# investigator_control_board.net
KiCad netlist of a schematic drawn in Altium Designer
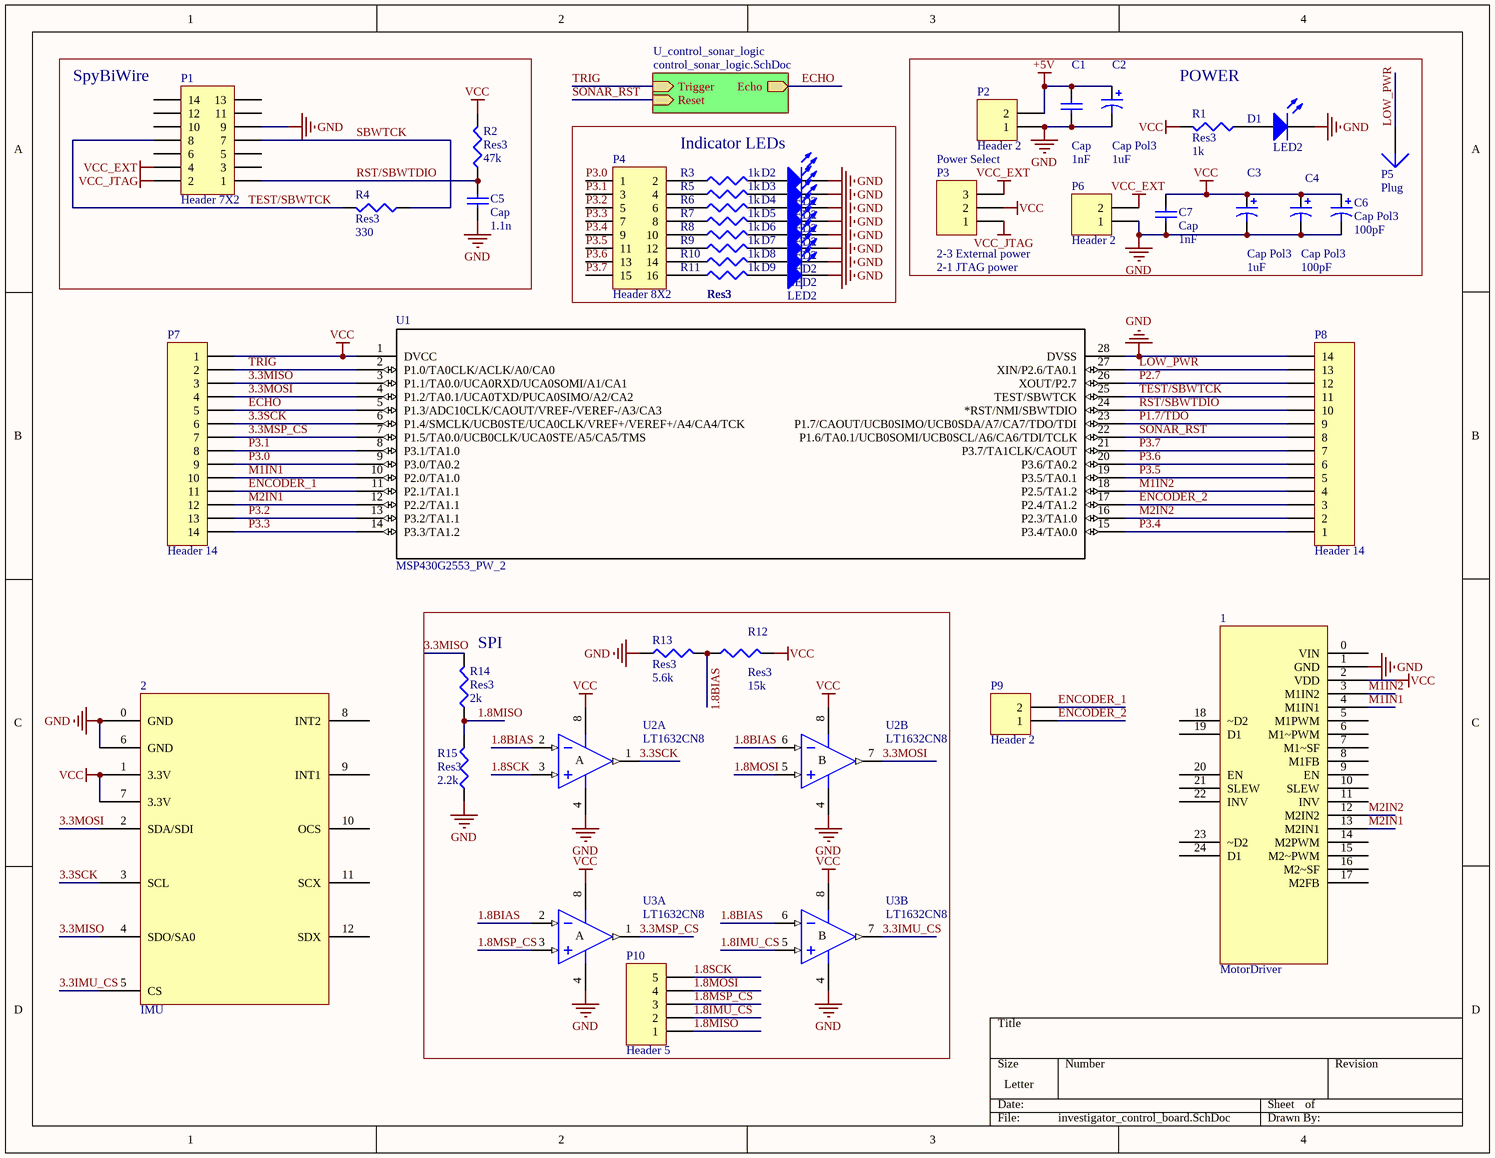
[diagram p0: investigator_control_board.SchDoc]

(export (version "E")
  (design (tool "Eeschema 10.0.6"))
  (components
    (comp (ref "1")
      (value "MotorDriver")
      (footprint "MotorControlHeader")
      (libsource (lib "control_board") (part "MotorDriver"))
    )
    (comp (ref "2") (value "IMU") (footprint "IMU") (libsource (lib "control_board") (part "IMU")))
    (comp (ref "C1")
      (value "Cap")
      (footprint "C0805")
      (description "Capacitor")
      (fields (field (name "ALTIUM_VALUE") "1nF") (field (name "PUBLISHER") "Altium Limited"))
      (libsource (lib "Miscellaneous Devices") (part "Cap"))
    )
    (comp (ref "C2")
      (value "Cap Pol3")
      (footprint "AXIAL-0.3")
      (description "Polarized Capacitor (Surface Mount)")
      (fields (field (name "ALTIUM_VALUE") "1uF") (field (name "PUBLISHER") "Altium Limited"))
      (libsource (lib "Miscellaneous Devices") (part "Cap Pol3"))
    )
    (comp (ref "C3")
      (value "Cap Pol3")
      (footprint "AXIAL-0.3")
      (description "Polarized Capacitor (Surface Mount)")
      (fields (field (name "ALTIUM_VALUE") "1uF") (field (name "PUBLISHER") "Altium Limited"))
      (libsource (lib "Miscellaneous Devices") (part "Cap Pol3"))
    )
    (comp (ref "C4")
      (value "Cap Pol3")
      (footprint "AXIAL-0.3")
      (description "Polarized Capacitor (Surface Mount)")
      (fields (field (name "ALTIUM_VALUE") "100pF") (field (name "PUBLISHER") "Altium Limited"))
      (libsource (lib "Miscellaneous Devices") (part "Cap Pol3"))
    )
    (comp (ref "C5")
      (value "Cap")
      (footprint "C0805")
      (description "Capacitor")
      (fields (field (name "ALTIUM_VALUE") "1.1n") (field (name "PUBLISHER") "Altium Limited"))
      (libsource (lib "Miscellaneous Devices") (part "Cap"))
    )
    (comp (ref "C6")
      (value "Cap Pol3")
      (footprint "AXIAL-0.3")
      (description "Polarized Capacitor (Surface Mount)")
      (fields (field (name "ALTIUM_VALUE") "100pF") (field (name "PUBLISHER") "Altium Limited"))
      (libsource (lib "Miscellaneous Devices") (part "Cap Pol3"))
    )
    (comp (ref "C7")
      (value "Cap")
      (footprint "C0805")
      (description "Capacitor")
      (fields (field (name "ALTIUM_VALUE") "1nF") (field (name "PUBLISHER") "Altium Limited"))
      (libsource (lib "Miscellaneous Devices") (part "Cap"))
    )
    (comp (ref "D1")
      (value "LED2")
      (footprint "3.2X1.6X1.1")
      (description "Typical RED, GREEN, YELLOW, AMBER GaAs LED")
      (fields (field (name "PUBLISHER") "Altium Limited"))
      (libsource (lib "Miscellaneous Devices") (part "LED2"))
    )
    (comp (ref "D2")
      (value "LED2")
      (footprint "3.2X1.6X1.1")
      (description "Typical RED, GREEN, YELLOW, AMBER GaAs LED")
      (fields (field (name "PUBLISHER") "Altium Limited"))
      (libsource (lib "Miscellaneous Devices") (part "LED2"))
    )
    (comp (ref "D3")
      (value "LED2")
      (footprint "3.2X1.6X1.1")
      (description "Typical RED, GREEN, YELLOW, AMBER GaAs LED")
      (fields (field (name "PUBLISHER") "Altium Limited"))
      (libsource (lib "Miscellaneous Devices") (part "LED2"))
    )
    (comp (ref "D4")
      (value "LED2")
      (footprint "3.2X1.6X1.1")
      (description "Typical RED, GREEN, YELLOW, AMBER GaAs LED")
      (fields (field (name "PUBLISHER") "Altium Limited"))
      (libsource (lib "Miscellaneous Devices") (part "LED2"))
    )
    (comp (ref "D5")
      (value "LED2")
      (footprint "3.2X1.6X1.1")
      (description "Typical RED, GREEN, YELLOW, AMBER GaAs LED")
      (fields (field (name "PUBLISHER") "Altium Limited"))
      (libsource (lib "Miscellaneous Devices") (part "LED2"))
    )
    (comp (ref "D6")
      (value "LED2")
      (footprint "3.2X1.6X1.1")
      (description "Typical RED, GREEN, YELLOW, AMBER GaAs LED")
      (fields (field (name "PUBLISHER") "Altium Limited"))
      (libsource (lib "Miscellaneous Devices") (part "LED2"))
    )
    (comp (ref "D7")
      (value "LED2")
      (footprint "3.2X1.6X1.1")
      (description "Typical RED, GREEN, YELLOW, AMBER GaAs LED")
      (fields (field (name "PUBLISHER") "Altium Limited"))
      (libsource (lib "Miscellaneous Devices") (part "LED2"))
    )
    (comp (ref "D8")
      (value "LED2")
      (footprint "3.2X1.6X1.1")
      (description "Typical RED, GREEN, YELLOW, AMBER GaAs LED")
      (fields (field (name "PUBLISHER") "Altium Limited"))
      (libsource (lib "Miscellaneous Devices") (part "LED2"))
    )
    (comp (ref "D9")
      (value "LED2")
      (footprint "3.2X1.6X1.1")
      (description "Typical RED, GREEN, YELLOW, AMBER GaAs LED")
      (fields (field (name "PUBLISHER") "Altium Limited"))
      (libsource (lib "Miscellaneous Devices") (part "LED2"))
    )
    (comp (ref "P1")
      (value "Header 7X2")
      (footprint "HDR2X7")
      (description "Header, 7-Pin, Dual row")
      (fields (field (name "PUBLISHER") "Altium Limited"))
      (libsource (lib "Miscellaneous Connectors") (part "Header 7X2"))
    )
    (comp (ref "P2")
      (value "Header 2")
      (footprint "HDR1X2")
      (description "Header, 2-Pin")
      (fields (field (name "PUBLISHER") "Altium Limited"))
      (libsource (lib "Miscellaneous Connectors") (part "Header 2"))
    )
    (comp (ref "P3")
      (value "Power Select")
      (footprint "HDR1X3")
      (description "Header, 3-Pin")
      (fields (field (name "PUBLISHER") "Altium Limited"))
      (libsource (lib "Miscellaneous Connectors") (part "Header 3"))
    )
    (comp (ref "P4")
      (value "Header 8X2")
      (footprint "HDR2X8")
      (description "Header, 8-Pin, Dual row")
      (fields (field (name "PUBLISHER") "Altium Limited"))
      (libsource (lib "Miscellaneous Connectors") (part "Header 8X2"))
    )
    (comp (ref "P5")
      (value "Plug")
      (footprint "PIN1")
      (fields (field (name "PUBLISHER") "Altium Limited"))
      (libsource (lib "Miscellaneous Connectors") (part "Plug"))
    )
    (comp (ref "P6")
      (value "Header 2")
      (footprint "HDR1X2")
      (description "Header, 2-Pin")
      (fields (field (name "PUBLISHER") "Altium Limited"))
      (libsource (lib "Miscellaneous Connectors") (part "Header 2"))
    )
    (comp (ref "P7")
      (value "Header 14")
      (footprint "HDR1X14")
      (description "Header, 14-Pin")
      (fields (field (name "PUBLISHER") "Altium Limited"))
      (libsource (lib "") (part "Header 14_1"))
    )
    (comp (ref "P8")
      (value "Header 14")
      (footprint "HDR1X14")
      (description "Header, 14-Pin")
      (fields (field (name "PUBLISHER") "Altium Limited"))
      (libsource (lib "Miscellaneous Connectors") (part "Header 14"))
    )
    (comp (ref "P9")
      (value "Header 2")
      (footprint "HDR1X2")
      (description "Header, 2-Pin")
      (fields (field (name "PUBLISHER") "Altium Limited"))
      (libsource (lib "Miscellaneous Connectors") (part "Header 2"))
    )
    (comp (ref "P10")
      (value "Header 5")
      (footprint "HDR1X5")
      (description "Header, 5-Pin")
      (fields (field (name "PUBLISHER") "Altium Limited"))
      (libsource (lib "Miscellaneous Connectors") (part "Header 5"))
    )
    (comp (ref "R1")
      (value "Res3")
      (footprint "6-0805_M")
      (description "Resistor")
      (fields (field (name "ALTIUM_VALUE") "1k") (field (name "PUBLISHER") "Altium Limited"))
      (libsource (lib "Miscellaneous Devices") (part "Res3"))
    )
    (comp (ref "R2")
      (value "Res3")
      (footprint "6-0805_M")
      (description "Resistor")
      (fields (field (name "ALTIUM_VALUE") "47k") (field (name "PUBLISHER") "Altium Limited"))
      (libsource (lib "Miscellaneous Devices") (part "Res3"))
    )
    (comp (ref "R3")
      (value "Res3")
      (footprint "6-0805_N")
      (description "Resistor")
      (fields (field (name "ALTIUM_VALUE") "1k") (field (name "PUBLISHER") "Altium Limited"))
      (libsource (lib "Miscellaneous Devices") (part "Res3"))
    )
    (comp (ref "R4")
      (value "Res3")
      (footprint "6-0805_M")
      (description "Resistor")
      (fields (field (name "ALTIUM_VALUE") "330") (field (name "PUBLISHER") "Altium Limited"))
      (libsource (lib "Miscellaneous Devices") (part "Res3"))
    )
    (comp (ref "R5")
      (value "Res3")
      (footprint "6-0805_N")
      (description "Resistor")
      (fields (field (name "ALTIUM_VALUE") "1k") (field (name "PUBLISHER") "Altium Limited"))
      (libsource (lib "Miscellaneous Devices") (part "Res3"))
    )
    (comp (ref "R6")
      (value "Res3")
      (footprint "6-0805_N")
      (description "Resistor")
      (fields (field (name "ALTIUM_VALUE") "1k") (field (name "PUBLISHER") "Altium Limited"))
      (libsource (lib "Miscellaneous Devices") (part "Res3"))
    )
    (comp (ref "R7")
      (value "Res3")
      (footprint "6-0805_N")
      (description "Resistor")
      (fields (field (name "ALTIUM_VALUE") "1k") (field (name "PUBLISHER") "Altium Limited"))
      (libsource (lib "Miscellaneous Devices") (part "Res3"))
    )
    (comp (ref "R8")
      (value "Res3")
      (footprint "6-0805_N")
      (description "Resistor")
      (fields (field (name "ALTIUM_VALUE") "1k") (field (name "PUBLISHER") "Altium Limited"))
      (libsource (lib "Miscellaneous Devices") (part "Res3"))
    )
    (comp (ref "R9")
      (value "Res3")
      (footprint "6-0805_N")
      (description "Resistor")
      (fields (field (name "ALTIUM_VALUE") "1k") (field (name "PUBLISHER") "Altium Limited"))
      (libsource (lib "Miscellaneous Devices") (part "Res3"))
    )
    (comp (ref "R10")
      (value "Res3")
      (footprint "6-0805_N")
      (description "Resistor")
      (fields (field (name "ALTIUM_VALUE") "1k") (field (name "PUBLISHER") "Altium Limited"))
      (libsource (lib "Miscellaneous Devices") (part "Res3"))
    )
    (comp (ref "R11")
      (value "Res3")
      (footprint "6-0805_N")
      (description "Resistor")
      (fields (field (name "ALTIUM_VALUE") "1k") (field (name "PUBLISHER") "Altium Limited"))
      (libsource (lib "Miscellaneous Devices") (part "Res3"))
    )
    (comp (ref "R12")
      (value "Res3")
      (footprint "6-0805_N")
      (description "Resistor")
      (fields (field (name "ALTIUM_VALUE") "15k") (field (name "PUBLISHER") "Altium Limited"))
      (libsource (lib "Miscellaneous Devices") (part "Res3"))
    )
    (comp (ref "R13")
      (value "Res3")
      (footprint "6-0805_N")
      (description "Resistor")
      (fields (field (name "ALTIUM_VALUE") "5.6k") (field (name "PUBLISHER") "Altium Limited"))
      (libsource (lib "Miscellaneous Devices") (part "Res3"))
    )
    (comp (ref "R14")
      (value "Res3")
      (footprint "6-0805_N")
      (description "Resistor")
      (fields (field (name "ALTIUM_VALUE") "2k") (field (name "PUBLISHER") "Altium Limited"))
      (libsource (lib "Miscellaneous Devices") (part "Res3"))
    )
    (comp (ref "R15")
      (value "Res3")
      (footprint "6-0805_N")
      (description "Resistor")
      (fields (field (name "ALTIUM_VALUE") "2.2k") (field (name "PUBLISHER") "Altium Limited"))
      (libsource (lib "Miscellaneous Devices") (part "Res3"))
    )
    (comp (ref "U1")
      (value "MSP430G2553_PW_2")
      (footprint "PW28")
      (description "Imported")
      (fields
        (field (name "MANUFACTURER_PART_NUMBER") "msp430g2553_pw_28")
        (field (name "GENERIC_PART_NUMBER") "MSP430G2553")
      )
      (libsource (lib "MSP430G2253") (part "MSP430G2553_PW_2"))
    )
    (comp (ref "U2")
      (value "LT1632CN8")
      (footprint "DIP-8")
      (description "45MHz, 45V/µs, Dual Rail-to-Rail Input and Output Precision Operational Amplifier")
      (fields (field (name "PUBLISHER") "Altium Limited"))
      (libsource (lib "ECE Lib (1)") (part "LT1632CN8"))
    )
    (comp (ref "U3")
      (value "LT1632CN8")
      (footprint "DIP-8")
      (description "45MHz, 45V/µs, Dual Rail-to-Rail Input and Output Precision Operational Amplifier")
      (fields (field (name "PUBLISHER") "Altium Limited"))
      (libsource (lib "ECE Lib (1)") (part "LT1632CN8"))
    )
  )
  (nets
    (net (code "1") (name "+5V") (class "Default")
      (node (ref "C1") (pin "2") (pinfunction "2_2") (pintype "passive"))
      (node (ref "C2") (pin "1") (pinfunction "1_1") (pintype "passive"))
      (node (ref "P2") (pin "2") (pinfunction "2_2") (pintype "passive"))
    )
    (net (code "2") (name "/1.8BIAS") (class "Default")
      (node (ref "R12") (pin "1") (pinfunction "1_1") (pintype "passive"))
      (node (ref "R13") (pin "2") (pinfunction "2_2") (pintype "passive"))
      (node (ref "U2") (pin "2") (pinfunction "IN-_2") (pintype "input"))
      (node (ref "U2") (pin "6") (pinfunction "IN-_6") (pintype "input"))
      (node (ref "U3") (pin "2") (pinfunction "IN-_2") (pintype "input"))
      (node (ref "U3") (pin "6") (pinfunction "IN-_6") (pintype "input"))
    )
    (net (code "3") (name "/1.8IMU_CS") (class "Default")
      (node (ref "P10") (pin "2") (pinfunction "2_2") (pintype "passive"))
      (node (ref "U3") (pin "5") (pinfunction "IN+_5") (pintype "input"))
    )
    (net (code "4") (name "/1.8MISO") (class "Default")
      (node (ref "P10") (pin "1") (pinfunction "1_1") (pintype "passive"))
      (node (ref "R14") (pin "1") (pinfunction "1_1") (pintype "passive"))
      (node (ref "R15") (pin "2") (pinfunction "2_2") (pintype "passive"))
    )
    (net (code "5") (name "/1.8MOSI") (class "Default")
      (node (ref "P10") (pin "4") (pinfunction "4_4") (pintype "passive"))
      (node (ref "U2") (pin "5") (pinfunction "IN+_5") (pintype "input"))
    )
    (net (code "6") (name "/1.8MSP_CS") (class "Default")
      (node (ref "P10") (pin "3") (pinfunction "3_3") (pintype "passive"))
      (node (ref "U3") (pin "3") (pinfunction "IN+_3") (pintype "input"))
    )
    (net (code "7") (name "/1.8SCK") (class "Default")
      (node (ref "P10") (pin "5") (pinfunction "5_5") (pintype "passive"))
      (node (ref "U2") (pin "3") (pinfunction "IN+_3") (pintype "input"))
    )
    (net (code "8") (name "/3.3IMU_CS") (class "Default")
      (node (ref "2") (pin "5") (pinfunction "CS_5") (pintype "passive"))
      (node (ref "U3") (pin "7") (pinfunction "OUT_7") (pintype "output"))
    )
    (net (code "9") (name "/3.3MISO") (class "Default")
      (node (ref "2") (pin "4") (pinfunction "SDO/SA0_4") (pintype "passive"))
      (node (ref "P7") (pin "3") (pinfunction "3_3") (pintype "passive"))
      (node (ref "R14") (pin "2") (pinfunction "2_2") (pintype "passive"))
      (node (ref "U1") (pin "3") (pinfunction "P1.1/TA0.0/UCA0RXD/UCA0SOMI/A1/CA1_3") (pintype "bidirectional"))
    )
    (net (code "10") (name "/3.3MOSI") (class "Default")
      (node (ref "2") (pin "2") (pinfunction "SDA/SDI_2") (pintype "passive"))
      (node (ref "P7") (pin "4") (pinfunction "4_4") (pintype "passive"))
      (node (ref "U1") (pin "4") (pinfunction "P1.2/TA0.1/UCA0TXD/PUCA0SIMO/A2/CA2_4") (pintype "bidirectional"))
      (node (ref "U2") (pin "7") (pinfunction "OUT_7") (pintype "output"))
    )
    (net (code "11") (name "/3.3MSP_CS") (class "Default")
      (node (ref "P7") (pin "7") (pinfunction "7_7") (pintype "passive"))
      (node (ref "U1") (pin "7") (pinfunction "P1.5/TA0.0/UCB0CLK/UCA0STE/A5/CA5/TMS_7") (pintype "bidirectional"))
      (node (ref "U3") (pin "1") (pinfunction "OUT_1") (pintype "output"))
    )
    (net (code "12") (name "/3.3SCK") (class "Default")
      (node (ref "2") (pin "3") (pinfunction "SCL_3") (pintype "passive"))
      (node (ref "P7") (pin "6") (pinfunction "6_6") (pintype "passive"))
      (node (ref "U1") (pin "6") (pinfunction "P1.4/SMCLK/UCB0STE/UCA0CLK/VREF+/VEREF+/A4/CA4/TCK_6") (pintype "bidirectional"))
      (node (ref "U2") (pin "1") (pinfunction "OUT_1") (pintype "output"))
    )
    (net (code "13") (name "/ECHO") (class "Default")
      (node (ref "P7") (pin "5") (pinfunction "5_5") (pintype "passive"))
      (node (ref "U1") (pin "5") (pinfunction "P1.3/ADC10CLK/CAOUT/VREF-/VEREF-/A3/CA3_5") (pintype "bidirectional"))
    )
    (net (code "14") (name "/ENCODER_1") (class "Default")
      (node (ref "P7") (pin "11") (pinfunction "11_11") (pintype "passive"))
      (node (ref "P9") (pin "2") (pinfunction "2_2") (pintype "passive"))
      (node (ref "U1") (pin "11") (pinfunction "P2.1/TA1.1_11") (pintype "bidirectional"))
    )
    (net (code "15") (name "/ENCODER_2") (class "Default")
      (node (ref "P8") (pin "3") (pinfunction "3_3") (pintype "passive"))
      (node (ref "P9") (pin "1") (pinfunction "1_1") (pintype "passive"))
      (node (ref "U1") (pin "17") (pinfunction "P2.4/TA1.2_17") (pintype "bidirectional"))
    )
    (net (code "16") (name "/LOW_PWR") (class "Default")
      (node (ref "P5") (pin "1") (pinfunction "1_1") (pintype "passive"))
      (node (ref "P8") (pin "13") (pinfunction "13_13") (pintype "passive"))
      (node (ref "U1") (pin "27") (pinfunction "XIN/P2.6/TA0.1_27") (pintype "bidirectional"))
    )
    (net (code "17") (name "/M1IN1") (class "Default")
      (node (ref "1") (pin "4") (pinfunction "M1IN1_4") (pintype "passive"))
      (node (ref "P7") (pin "10") (pinfunction "10_10") (pintype "passive"))
      (node (ref "U1") (pin "10") (pinfunction "P2.0/TA1.0_10") (pintype "bidirectional"))
    )
    (net (code "18") (name "/M1IN2") (class "Default")
      (node (ref "1") (pin "3") (pinfunction "M1IN2_3") (pintype "passive"))
      (node (ref "P8") (pin "4") (pinfunction "4_4") (pintype "passive"))
      (node (ref "U1") (pin "18") (pinfunction "P2.5/TA1.2_18") (pintype "bidirectional"))
    )
    (net (code "19") (name "/M2IN1") (class "Default")
      (node (ref "1") (pin "13") (pinfunction "M2IN1_13") (pintype "passive"))
      (node (ref "P7") (pin "12") (pinfunction "12_12") (pintype "passive"))
      (node (ref "U1") (pin "12") (pinfunction "P2.2/TA1.1_12") (pintype "bidirectional"))
    )
    (net (code "20") (name "/M2IN2") (class "Default")
      (node (ref "1") (pin "12") (pinfunction "M2IN2_12") (pintype "passive"))
      (node (ref "P8") (pin "2") (pinfunction "2_2") (pintype "passive"))
      (node (ref "U1") (pin "16") (pinfunction "P2.3/TA1.0_16") (pintype "bidirectional"))
    )
    (net (code "21") (name "/P1.7{slash}TDO") (class "Default")
      (node (ref "P8") (pin "9") (pinfunction "9_9") (pintype "passive"))
      (node (ref "U1") (pin "23") (pinfunction "P1.7/CAOUT/UCB0SIMO/UCB0SDA/A7/CA7/TDO/TDI_23") (pintype "bidirectional"))
    )
    (net (code "22") (name "/P2.7") (class "Default")
      (node (ref "P8") (pin "12") (pinfunction "12_12") (pintype "passive"))
      (node (ref "U1") (pin "26") (pinfunction "XOUT/P2.7_26") (pintype "bidirectional"))
    )
    (net (code "23") (name "/P3.0") (class "Default")
      (node (ref "P4") (pin "1") (pinfunction "1_1") (pintype "passive"))
      (node (ref "P7") (pin "9") (pinfunction "9_9") (pintype "passive"))
      (node (ref "U1") (pin "9") (pinfunction "P3.0/TA0.2_9") (pintype "bidirectional"))
    )
    (net (code "24") (name "/P3.1") (class "Default")
      (node (ref "P4") (pin "3") (pinfunction "3_3") (pintype "passive"))
      (node (ref "P7") (pin "8") (pinfunction "8_8") (pintype "passive"))
      (node (ref "U1") (pin "8") (pinfunction "P3.1/TA1.0_8") (pintype "bidirectional"))
    )
    (net (code "25") (name "/P3.2") (class "Default")
      (node (ref "P4") (pin "5") (pinfunction "5_5") (pintype "passive"))
      (node (ref "P7") (pin "13") (pinfunction "13_13") (pintype "passive"))
      (node (ref "U1") (pin "13") (pinfunction "P3.2/TA1.1_13") (pintype "bidirectional"))
    )
    (net (code "26") (name "/P3.3") (class "Default")
      (node (ref "P4") (pin "7") (pinfunction "7_7") (pintype "passive"))
      (node (ref "P7") (pin "14") (pinfunction "14_14") (pintype "passive"))
      (node (ref "U1") (pin "14") (pinfunction "P3.3/TA1.2_14") (pintype "bidirectional"))
    )
    (net (code "27") (name "/P3.4") (class "Default")
      (node (ref "P4") (pin "9") (pinfunction "9_9") (pintype "passive"))
      (node (ref "P8") (pin "1") (pinfunction "1_1") (pintype "passive"))
      (node (ref "U1") (pin "15") (pinfunction "P3.4/TA0.0_15") (pintype "bidirectional"))
    )
    (net (code "28") (name "/P3.5") (class "Default")
      (node (ref "P4") (pin "11") (pinfunction "11_11") (pintype "passive"))
      (node (ref "P8") (pin "5") (pinfunction "5_5") (pintype "passive"))
      (node (ref "U1") (pin "19") (pinfunction "P3.5/TA0.1_19") (pintype "bidirectional"))
    )
    (net (code "29") (name "/P3.6") (class "Default")
      (node (ref "P4") (pin "13") (pinfunction "13_13") (pintype "passive"))
      (node (ref "P8") (pin "6") (pinfunction "6_6") (pintype "passive"))
      (node (ref "U1") (pin "20") (pinfunction "P3.6/TA0.2_20") (pintype "bidirectional"))
    )
    (net (code "30") (name "/P3.7") (class "Default")
      (node (ref "P4") (pin "15") (pinfunction "15_15") (pintype "passive"))
      (node (ref "P8") (pin "7") (pinfunction "7_7") (pintype "passive"))
      (node (ref "U1") (pin "21") (pinfunction "P3.7/TA1CLK/CAOUT_21") (pintype "bidirectional"))
    )
    (net (code "31") (name "/RST{slash}SBWTDIO") (class "Default")
      (node (ref "C5") (pin "2") (pinfunction "2_2") (pintype "passive"))
      (node (ref "P1") (pin "1") (pinfunction "1_1") (pintype "passive"))
      (node (ref "P8") (pin "10") (pinfunction "10_10") (pintype "passive"))
      (node (ref "R2") (pin "1") (pinfunction "1_1") (pintype "passive"))
      (node (ref "U1") (pin "24") (pinfunction "*RST/NMI/SBWTDIO_24") (pintype "bidirectional"))
    )
    (net (code "32") (name "/SBWTCK") (class "Default")
      (node (ref "P1") (pin "7") (pinfunction "7_7") (pintype "passive"))
      (node (ref "R4") (pin "1") (pinfunction "1_1") (pintype "passive"))
    )
    (net (code "33") (name "/SONAR_RST") (class "Default")
      (node (ref "P8") (pin "8") (pinfunction "8_8") (pintype "passive"))
      (node (ref "U1") (pin "22") (pinfunction "P1.6/TA0.1/UCB0SOMI/UCB0SCL/A6/CA6/TDI/TCLK_22") (pintype "bidirectional"))
    )
    (net (code "34") (name "/TEST{slash}SBWTCK") (class "Default")
      (node (ref "P1") (pin "8") (pinfunction "8_8") (pintype "passive"))
      (node (ref "P8") (pin "11") (pinfunction "11_11") (pintype "passive"))
      (node (ref "R4") (pin "2") (pinfunction "2_2") (pintype "passive"))
      (node (ref "U1") (pin "25") (pinfunction "TEST/SBWTCK_25") (pintype "bidirectional"))
    )
    (net (code "35") (name "/TRIG") (class "Default")
      (node (ref "P7") (pin "2") (pinfunction "2_2") (pintype "passive"))
      (node (ref "U1") (pin "2") (pinfunction "P1.0/TA0CLK/ACLK/A0/CA0_2") (pintype "bidirectional"))
    )
    (net (code "36") (name "GND") (class "Default")
      (node (ref "1") (pin "1") (pinfunction "GND_1") (pintype "passive"))
      (node (ref "2") (pin "0") (pinfunction "GND_0") (pintype "passive"))
      (node (ref "2") (pin "6") (pinfunction "GND_6") (pintype "passive"))
      (node (ref "C1") (pin "1") (pinfunction "1_1") (pintype "passive"))
      (node (ref "C2") (pin "2") (pinfunction "2_2") (pintype "passive"))
      (node (ref "C3") (pin "2") (pinfunction "2_2") (pintype "passive"))
      (node (ref "C4") (pin "2") (pinfunction "2_2") (pintype "passive"))
      (node (ref "C5") (pin "1") (pinfunction "1_1") (pintype "passive"))
      (node (ref "C6") (pin "2") (pinfunction "2_2") (pintype "passive"))
      (node (ref "C7") (pin "1") (pinfunction "1_1") (pintype "passive"))
      (node (ref "D1") (pin "2") (pinfunction "K_2") (pintype "passive"))
      (node (ref "D2") (pin "2") (pinfunction "K_2") (pintype "passive"))
      (node (ref "D3") (pin "2") (pinfunction "K_2") (pintype "passive"))
      (node (ref "D4") (pin "2") (pinfunction "K_2") (pintype "passive"))
      (node (ref "D5") (pin "2") (pinfunction "K_2") (pintype "passive"))
      (node (ref "D6") (pin "2") (pinfunction "K_2") (pintype "passive"))
      (node (ref "D7") (pin "2") (pinfunction "K_2") (pintype "passive"))
      (node (ref "D8") (pin "2") (pinfunction "K_2") (pintype "passive"))
      (node (ref "D9") (pin "2") (pinfunction "K_2") (pintype "passive"))
      (node (ref "P1") (pin "9") (pinfunction "9_9") (pintype "passive"))
      (node (ref "P2") (pin "1") (pinfunction "1_1") (pintype "passive"))
      (node (ref "P6") (pin "1") (pinfunction "1_1") (pintype "passive"))
      (node (ref "P8") (pin "14") (pinfunction "14_14") (pintype "passive"))
      (node (ref "R13") (pin "1") (pinfunction "1_1") (pintype "passive"))
      (node (ref "R15") (pin "1") (pinfunction "1_1") (pintype "passive"))
      (node (ref "U1") (pin "28") (pinfunction "DVSS_28") (pintype "power_in"))
      (node (ref "U2") (pin "4") (pinfunction "V-_4") (pintype "power_in"))
      (node (ref "U3") (pin "4") (pinfunction "V-_4") (pintype "power_in"))
    )
    (net (code "37") (name "Net-(D1-A)") (class "Default")
      (node (ref "D1") (pin "1") (pinfunction "A_1") (pintype "passive"))
      (node (ref "R1") (pin "1") (pinfunction "1_1") (pintype "passive"))
    )
    (net (code "38") (name "Net-(D2-A)") (class "Default")
      (node (ref "D2") (pin "1") (pinfunction "A_1") (pintype "passive"))
      (node (ref "R3") (pin "2") (pinfunction "2_2") (pintype "passive"))
    )
    (net (code "39") (name "Net-(D3-A)") (class "Default")
      (node (ref "D3") (pin "1") (pinfunction "A_1") (pintype "passive"))
      (node (ref "R5") (pin "2") (pinfunction "2_2") (pintype "passive"))
    )
    (net (code "40") (name "Net-(D4-A)") (class "Default")
      (node (ref "D4") (pin "1") (pinfunction "A_1") (pintype "passive"))
      (node (ref "R6") (pin "2") (pinfunction "2_2") (pintype "passive"))
    )
    (net (code "41") (name "Net-(D5-A)") (class "Default")
      (node (ref "D5") (pin "1") (pinfunction "A_1") (pintype "passive"))
      (node (ref "R7") (pin "2") (pinfunction "2_2") (pintype "passive"))
    )
    (net (code "42") (name "Net-(D6-A)") (class "Default")
      (node (ref "D6") (pin "1") (pinfunction "A_1") (pintype "passive"))
      (node (ref "R8") (pin "2") (pinfunction "2_2") (pintype "passive"))
    )
    (net (code "43") (name "Net-(D7-A)") (class "Default")
      (node (ref "D7") (pin "1") (pinfunction "A_1") (pintype "passive"))
      (node (ref "R9") (pin "2") (pinfunction "2_2") (pintype "passive"))
    )
    (net (code "44") (name "Net-(D8-A)") (class "Default")
      (node (ref "D8") (pin "1") (pinfunction "A_1") (pintype "passive"))
      (node (ref "R10") (pin "2") (pinfunction "2_2") (pintype "passive"))
    )
    (net (code "45") (name "Net-(D9-A)") (class "Default")
      (node (ref "D9") (pin "1") (pinfunction "A_1") (pintype "passive"))
      (node (ref "R11") (pin "2") (pinfunction "2_2") (pintype "passive"))
    )
    (net (code "46") (name "Net-(P4-Pad2)") (class "Default")
      (node (ref "P4") (pin "2") (pinfunction "2_2") (pintype "passive"))
      (node (ref "R3") (pin "1") (pinfunction "1_1") (pintype "passive"))
    )
    (net (code "47") (name "Net-(P4-Pad4)") (class "Default")
      (node (ref "P4") (pin "4") (pinfunction "4_4") (pintype "passive"))
      (node (ref "R5") (pin "1") (pinfunction "1_1") (pintype "passive"))
    )
    (net (code "48") (name "Net-(P4-Pad6)") (class "Default")
      (node (ref "P4") (pin "6") (pinfunction "6_6") (pintype "passive"))
      (node (ref "R6") (pin "1") (pinfunction "1_1") (pintype "passive"))
    )
    (net (code "49") (name "Net-(P4-Pad8)") (class "Default")
      (node (ref "P4") (pin "8") (pinfunction "8_8") (pintype "passive"))
      (node (ref "R7") (pin "1") (pinfunction "1_1") (pintype "passive"))
    )
    (net (code "50") (name "Net-(P4-Pad10)") (class "Default")
      (node (ref "P4") (pin "10") (pinfunction "10_10") (pintype "passive"))
      (node (ref "R8") (pin "1") (pinfunction "1_1") (pintype "passive"))
    )
    (net (code "51") (name "Net-(P4-Pad12)") (class "Default")
      (node (ref "P4") (pin "12") (pinfunction "12_12") (pintype "passive"))
      (node (ref "R9") (pin "1") (pinfunction "1_1") (pintype "passive"))
    )
    (net (code "52") (name "Net-(P4-Pad14)") (class "Default")
      (node (ref "P4") (pin "14") (pinfunction "14_14") (pintype "passive"))
      (node (ref "R10") (pin "1") (pinfunction "1_1") (pintype "passive"))
    )
    (net (code "53") (name "Net-(P4-Pad16)") (class "Default")
      (node (ref "P4") (pin "16") (pinfunction "16_16") (pintype "passive"))
      (node (ref "R11") (pin "1") (pinfunction "1_1") (pintype "passive"))
    )
    (net (code "54") (name "VCC") (class "Default")
      (node (ref "1") (pin "2") (pinfunction "VDD_2") (pintype "passive"))
      (node (ref "2") (pin "1") (pinfunction "3.3V_1") (pintype "passive"))
      (node (ref "2") (pin "7") (pinfunction "3.3V_7") (pintype "passive"))
      (node (ref "C3") (pin "1") (pinfunction "1_1") (pintype "passive"))
      (node (ref "C4") (pin "1") (pinfunction "1_1") (pintype "passive"))
      (node (ref "C6") (pin "1") (pinfunction "1_1") (pintype "passive"))
      (node (ref "C7") (pin "2") (pinfunction "2_2") (pintype "passive"))
      (node (ref "P3") (pin "2") (pinfunction "2_2") (pintype "passive"))
      (node (ref "P7") (pin "1") (pinfunction "1_1") (pintype "passive"))
      (node (ref "R1") (pin "2") (pinfunction "2_2") (pintype "passive"))
      (node (ref "R12") (pin "2") (pinfunction "2_2") (pintype "passive"))
      (node (ref "R2") (pin "2") (pinfunction "2_2") (pintype "passive"))
      (node (ref "U1") (pin "1") (pinfunction "DVCC_1") (pintype "power_in"))
      (node (ref "U2") (pin "8") (pinfunction "V+_8") (pintype "power_in"))
      (node (ref "U3") (pin "8") (pinfunction "V+_8") (pintype "power_in"))
    )
    (net (code "55") (name "VCC_EXT") (class "Default")
      (node (ref "P1") (pin "4") (pinfunction "4_4") (pintype "passive"))
      (node (ref "P3") (pin "3") (pinfunction "3_3") (pintype "passive"))
      (node (ref "P6") (pin "2") (pinfunction "2_2") (pintype "passive"))
    )
    (net (code "56") (name "VCC_JTAG") (class "Default")
      (node (ref "P1") (pin "2") (pinfunction "2_2") (pintype "passive"))
      (node (ref "P3") (pin "1") (pinfunction "1_1") (pintype "passive"))
    )
    (net (code "57") (name "unconnected-(1-D1-Pad19)") (class "Default")
      (node (ref "1") (pin "19") (pinfunction "D1_19") (pintype "passive"))
    )
    (net (code "58") (name "unconnected-(1-D1-Pad24)") (class "Default")
      (node (ref "1") (pin "24") (pinfunction "D1_24") (pintype "passive"))
    )
    (net (code "59") (name "unconnected-(1-EN-Pad9)") (class "Default")
      (node (ref "1") (pin "9") (pinfunction "EN_9") (pintype "passive"))
    )
    (net (code "60") (name "unconnected-(1-EN-Pad20)") (class "Default")
      (node (ref "1") (pin "20") (pinfunction "EN_20") (pintype "passive"))
    )
    (net (code "61") (name "unconnected-(1-INV-Pad11)") (class "Default")
      (node (ref "1") (pin "11") (pinfunction "INV_11") (pintype "passive"))
    )
    (net (code "62") (name "unconnected-(1-INV-Pad22)") (class "Default")
      (node (ref "1") (pin "22") (pinfunction "INV_22") (pintype "passive"))
    )
    (net (code "63") (name "unconnected-(1-M1FB-Pad8)") (class "Default")
      (node (ref "1") (pin "8") (pinfunction "M1FB_8") (pintype "passive"))
    )
    (net (code "64") (name "unconnected-(1-M1PWM-Pad5)") (class "Default")
      (node (ref "1") (pin "5") (pinfunction "M1PWM_5") (pintype "passive"))
    )
    (net (code "65") (name "unconnected-(1-M1~PWM-Pad6)") (class "Default")
      (node (ref "1") (pin "6") (pinfunction "M1~PWM_6") (pintype "passive"))
    )
    (net (code "66") (name "unconnected-(1-M1~SF-Pad7)") (class "Default")
      (node (ref "1") (pin "7") (pinfunction "M1~SF_7") (pintype "passive"))
    )
    (net (code "67") (name "unconnected-(1-M2FB-Pad17)") (class "Default")
      (node (ref "1") (pin "17") (pinfunction "M2FB_17") (pintype "passive"))
    )
    (net (code "68") (name "unconnected-(1-M2PWM-Pad14)") (class "Default")
      (node (ref "1") (pin "14") (pinfunction "M2PWM_14") (pintype "passive"))
    )
    (net (code "69") (name "unconnected-(1-M2~PWM-Pad15)") (class "Default")
      (node (ref "1") (pin "15") (pinfunction "M2~PWM_15") (pintype "passive"))
    )
    (net (code "70") (name "unconnected-(1-M2~SF-Pad16)") (class "Default")
      (node (ref "1") (pin "16") (pinfunction "M2~SF_16") (pintype "passive"))
    )
    (net (code "71") (name "unconnected-(1-SLEW-Pad10)") (class "Default")
      (node (ref "1") (pin "10") (pinfunction "SLEW_10") (pintype "passive"))
    )
    (net (code "72") (name "unconnected-(1-SLEW-Pad21)") (class "Default")
      (node (ref "1") (pin "21") (pinfunction "SLEW_21") (pintype "passive"))
    )
    (net (code "73") (name "unconnected-(1-VIN-Pad0)") (class "Default")
      (node (ref "1") (pin "0") (pinfunction "VIN_0") (pintype "passive"))
    )
    (net (code "74") (name "unconnected-(1-~D2-Pad18)") (class "Default")
      (node (ref "1") (pin "18") (pinfunction "~D2_18") (pintype "passive"))
    )
    (net (code "75") (name "unconnected-(1-~D2-Pad23)") (class "Default")
      (node (ref "1") (pin "23") (pinfunction "~D2_23") (pintype "passive"))
    )
    (net (code "76") (name "unconnected-(2-INT1-Pad9)") (class "Default")
      (node (ref "2") (pin "9") (pinfunction "INT1_9") (pintype "passive"))
    )
    (net (code "77") (name "unconnected-(2-INT2-Pad8)") (class "Default")
      (node (ref "2") (pin "8") (pinfunction "INT2_8") (pintype "passive"))
    )
    (net (code "78") (name "unconnected-(2-OCS-Pad10)") (class "Default")
      (node (ref "2") (pin "10") (pinfunction "OCS_10") (pintype "passive"))
    )
    (net (code "79") (name "unconnected-(2-SCX-Pad11)") (class "Default")
      (node (ref "2") (pin "11") (pinfunction "SCX_11") (pintype "passive"))
    )
    (net (code "80") (name "unconnected-(2-SDX-Pad12)") (class "Default")
      (node (ref "2") (pin "12") (pinfunction "SDX_12") (pintype "passive"))
    )
    (net (code "81") (name "unconnected-(P1-Pad3)") (class "Default")
      (node (ref "P1") (pin "3") (pinfunction "3_3") (pintype "passive"))
    )
    (net (code "82") (name "unconnected-(P1-Pad5)") (class "Default")
      (node (ref "P1") (pin "5") (pinfunction "5_5") (pintype "passive"))
    )
    (net (code "83") (name "unconnected-(P1-Pad6)") (class "Default")
      (node (ref "P1") (pin "6") (pinfunction "6_6") (pintype "passive"))
    )
    (net (code "84") (name "unconnected-(P1-Pad10)") (class "Default")
      (node (ref "P1") (pin "10") (pinfunction "10_10") (pintype "passive"))
    )
    (net (code "85") (name "unconnected-(P1-Pad11)") (class "Default")
      (node (ref "P1") (pin "11") (pinfunction "11_11") (pintype "passive"))
    )
    (net (code "86") (name "unconnected-(P1-Pad12)") (class "Default")
      (node (ref "P1") (pin "12") (pinfunction "12_12") (pintype "passive"))
    )
    (net (code "87") (name "unconnected-(P1-Pad13)") (class "Default")
      (node (ref "P1") (pin "13") (pinfunction "13_13") (pintype "passive"))
    )
    (net (code "88") (name "unconnected-(P1-Pad14)") (class "Default")
      (node (ref "P1") (pin "14") (pinfunction "14_14") (pintype "passive"))
    )
  )
)
